# SC_1.net
KiCad netlist of a schematic drawn in EAGLE
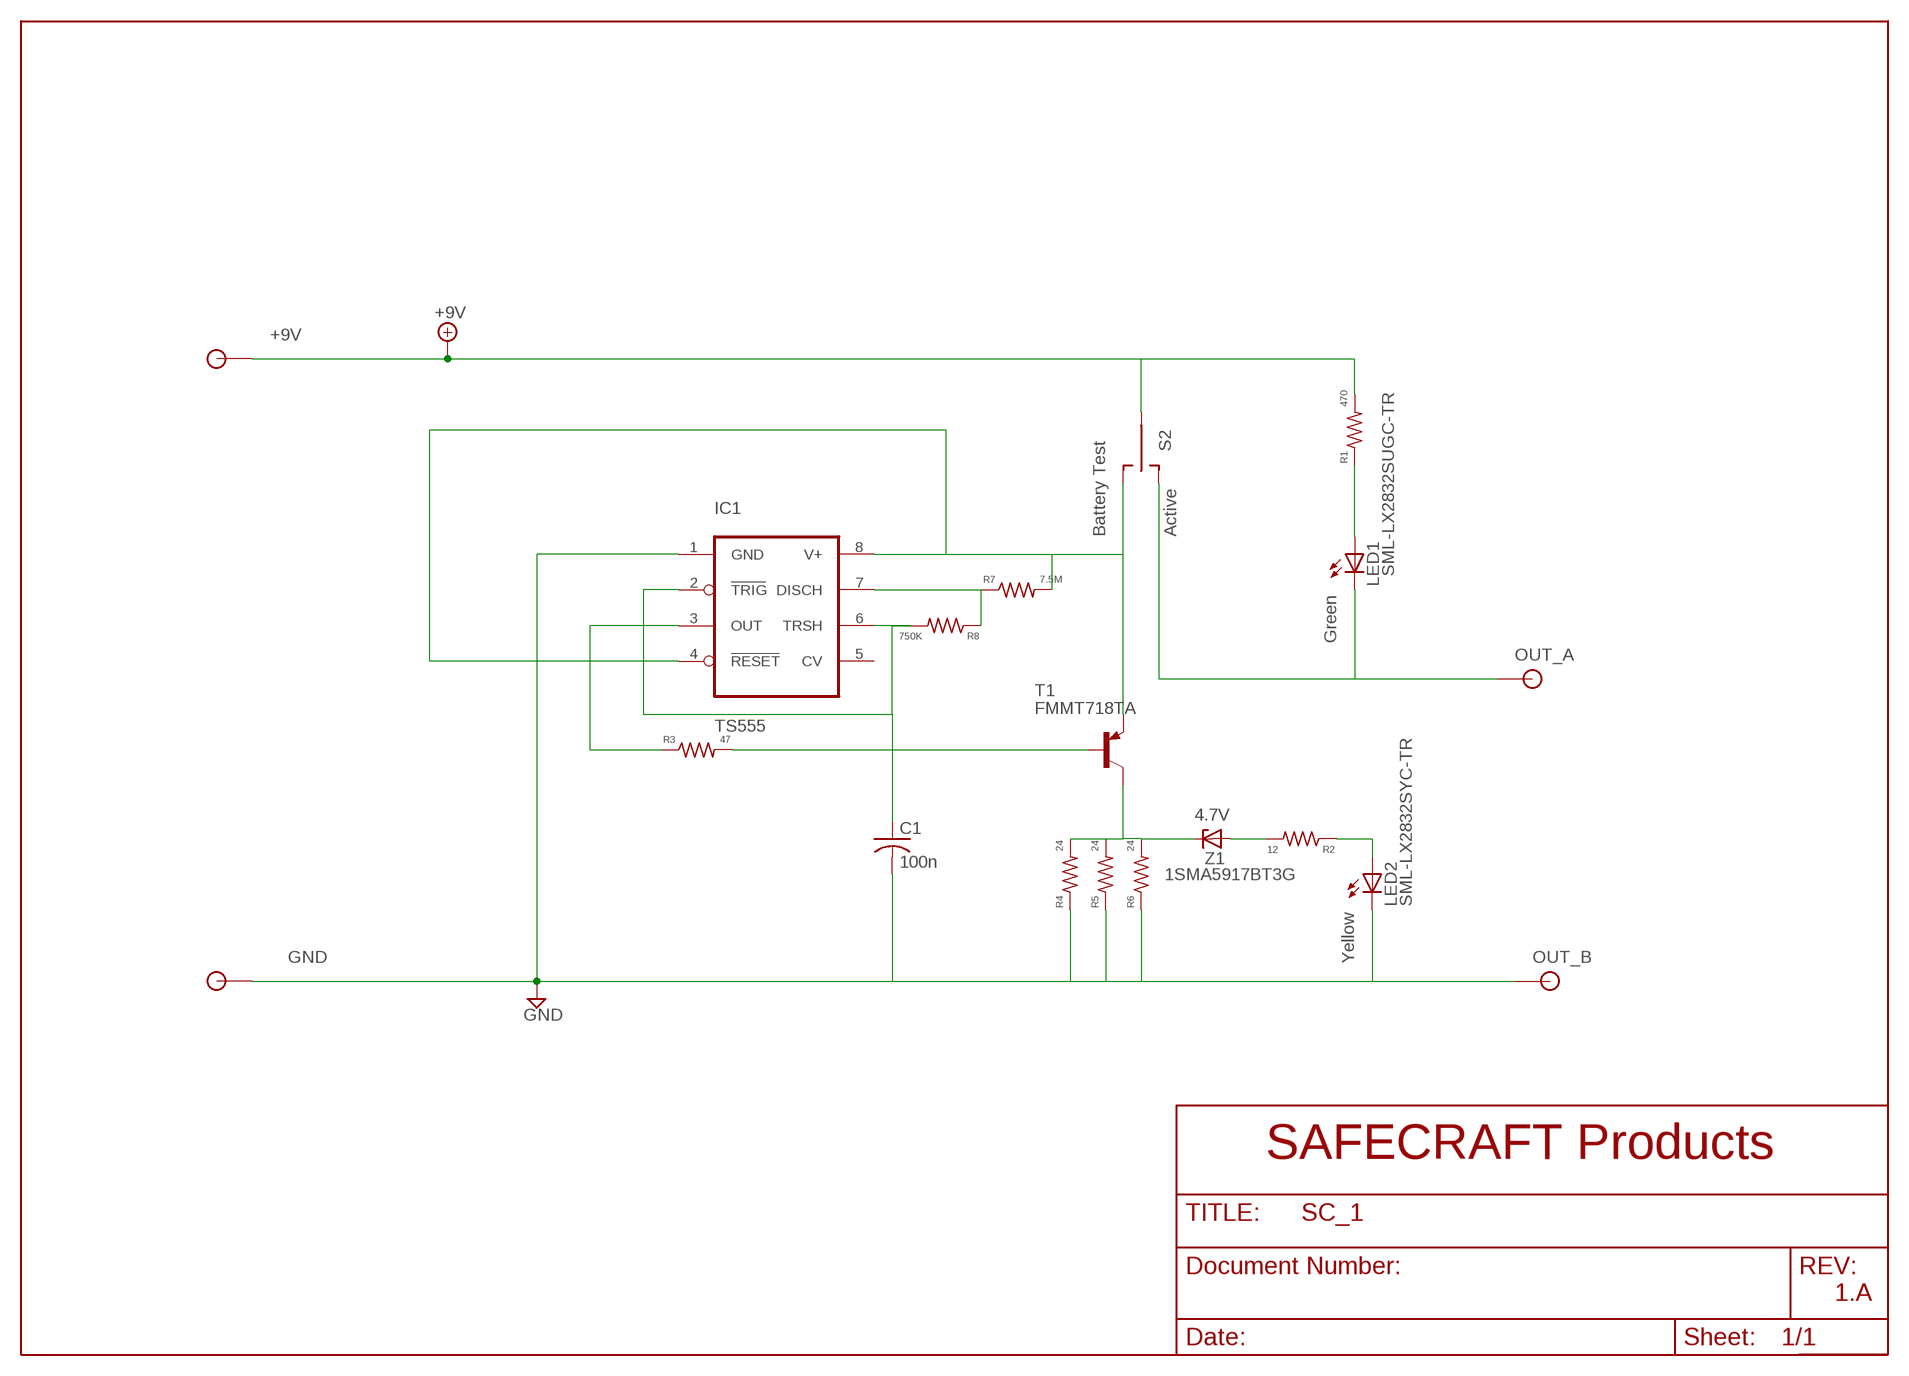
[diagram p0: schematic, sheet 1]

(export (version "E")
  (design (tool "Eeschema 10.0.6"))
  (components
    (comp (ref "C1")
      (value "100n")
      (footprint "eagle-import:C0805")
      (libsource (lib "eagle-import") (part "C-USC0805"))
    )
    (comp (ref "IC1")
      (value "TS555")
      (footprint "eagle-import:SO08")
      (libsource (lib "eagle-import") (part "ICM7555SO08"))
    )
    (comp (ref "LED1")
      (value "SML-LX2832SUGC-TR")
      (footprint "eagle-import:P-LCC-2")
      (libsource (lib "eagle-import") (part "LEDP-LCC-2"))
    )
    (comp (ref "LED2")
      (value "SML-LX2832SYC-TR")
      (footprint "eagle-import:P-LCC-2")
      (libsource (lib "eagle-import") (part "LEDP-LCC-2"))
    )
    (comp (ref "R1")
      (value "470")
      (footprint "eagle-import:R0805")
      (libsource (lib "eagle-import") (part "R-US_R0805"))
    )
    (comp (ref "R2")
      (value "12")
      (footprint "eagle-import:R0805")
      (libsource (lib "eagle-import") (part "R-US_R0805"))
    )
    (comp (ref "R3")
      (value "47")
      (footprint "eagle-import:R0805")
      (libsource (lib "eagle-import") (part "R-US_R0805"))
    )
    (comp (ref "R4")
      (value "24")
      (footprint "eagle-import:R1206")
      (libsource (lib "eagle-import") (part "R-US_R1206"))
    )
    (comp (ref "R5")
      (value "24")
      (footprint "eagle-import:R1206")
      (libsource (lib "eagle-import") (part "R-US_R1206"))
    )
    (comp (ref "R6")
      (value "24")
      (footprint "eagle-import:R1206")
      (libsource (lib "eagle-import") (part "R-US_R1206"))
    )
    (comp (ref "R7")
      (value "7.5M")
      (footprint "eagle-import:R0805")
      (libsource (lib "eagle-import") (part "R-US_R0805"))
    )
    (comp (ref "R8")
      (value "750K")
      (footprint "eagle-import:R0805")
      (libsource (lib "eagle-import") (part "R-US_R0805"))
    )
    (comp (ref "S2")
      (value "TL39POB")
      (footprint "eagle-import:TL3XPO_NOHOLES")
      (libsource (lib "eagle-import") (part "TL39POB"))
    )
    (comp (ref "T1")
      (value "FMMT718TA")
      (footprint "eagle-import:SOT23-BEC")
      (libsource (lib "eagle-import") (part "-PNP-SOT23-BECBC807-16"))
    )
    (comp (ref "U$1")
      (value "SOLDERPAD_NOHOLE")
      (footprint "eagle-import:SOLDERPAD_NOHOLES")
      (libsource (lib "eagle-import") (part "SOLDERPAD_NOHOLE"))
    )
    (comp (ref "U$2")
      (value "SOLDERPAD_NOHOLE")
      (footprint "eagle-import:SOLDERPAD_NOHOLES")
      (libsource (lib "eagle-import") (part "SOLDERPAD_NOHOLE"))
    )
    (comp (ref "U$3")
      (value "SOLDERPAD_NOHOLE")
      (footprint "eagle-import:SOLDERPAD_NOHOLES")
      (libsource (lib "eagle-import") (part "SOLDERPAD_NOHOLE"))
    )
    (comp (ref "U$4")
      (value "SOLDERPAD_NOHOLE")
      (footprint "eagle-import:SOLDERPAD_NOHOLES")
      (libsource (lib "eagle-import") (part "SOLDERPAD_NOHOLE"))
    )
    (comp (ref "Z1")
      (value "1SMA5917BT3G")
      (footprint "eagle-import:SMB")
      (libsource (lib "eagle-import") (part "ZENER-DIODESMB"))
    )
  )
  (nets
    (net (code "1") (name "+9V") (class "Default")
      (node (ref "R1") (pin "2") (pinfunction "2_2") (pintype "passive"))
      (node (ref "S2") (pin "P$2") (pinfunction "P_P$2") (pintype "passive"))
      (node (ref "U$3") (pin "P$1") (pinfunction "P$1_P$1") (pintype "bidirectional"))
    )
    (net (code "2") (name "/OUT_A") (class "Default")
      (node (ref "LED1") (pin "C") (pinfunction "C_C") (pintype "passive"))
      (node (ref "S2") (pin "P$1") (pinfunction "O_P$1") (pintype "passive"))
      (node (ref "U$1") (pin "P$1") (pinfunction "P$1_P$1") (pintype "bidirectional"))
    )
    (net (code "3") (name "GND") (class "Default")
      (node (ref "C1") (pin "2") (pinfunction "2_2") (pintype "passive"))
      (node (ref "IC1") (pin "1") (pinfunction "GND_1") (pintype "power_in"))
      (node (ref "LED2") (pin "C") (pinfunction "C_C") (pintype "passive"))
      (node (ref "R4") (pin "1") (pinfunction "1_1") (pintype "passive"))
      (node (ref "R5") (pin "1") (pinfunction "1_1") (pintype "passive"))
      (node (ref "R6") (pin "1") (pinfunction "1_1") (pintype "passive"))
      (node (ref "U$2") (pin "P$1") (pinfunction "P$1_P$1") (pintype "bidirectional"))
      (node (ref "U$4") (pin "P$1") (pinfunction "P$1_P$1") (pintype "bidirectional"))
    )
    (net (code "4") (name "Net-(IC1-DISCH)") (class "Default")
      (node (ref "IC1") (pin "7") (pinfunction "DISCH_7") (pintype "input"))
      (node (ref "R7") (pin "1") (pinfunction "1_1") (pintype "passive"))
      (node (ref "R8") (pin "1") (pinfunction "1_1") (pintype "passive"))
    )
    (net (code "5") (name "Net-(IC1-OUT)") (class "Default")
      (node (ref "IC1") (pin "3") (pinfunction "OUT_3") (pintype "output"))
      (node (ref "R3") (pin "1") (pinfunction "1_1") (pintype "passive"))
    )
    (net (code "6") (name "Net-(IC1-RESET)") (class "Default")
      (node (ref "IC1") (pin "4") (pinfunction "RESET_4") (pintype "input"))
      (node (ref "IC1") (pin "8") (pinfunction "V+_8") (pintype "power_in"))
      (node (ref "R7") (pin "2") (pinfunction "2_2") (pintype "passive"))
      (node (ref "S2") (pin "P$3") (pinfunction "S_P$3") (pintype "passive"))
      (node (ref "T1") (pin "E") (pinfunction "E_E") (pintype "passive"))
    )
    (net (code "7") (name "Net-(IC1-TRIG)") (class "Default")
      (node (ref "C1") (pin "1") (pinfunction "1_1") (pintype "passive"))
      (node (ref "IC1") (pin "2") (pinfunction "TRIG_2") (pintype "bidirectional"))
      (node (ref "IC1") (pin "6") (pinfunction "TRSH_6") (pintype "input"))
      (node (ref "R8") (pin "2") (pinfunction "2_2") (pintype "passive"))
    )
    (net (code "8") (name "Net-(LED1-PadA)") (class "Default")
      (node (ref "LED1") (pin "A") (pinfunction "A_A") (pintype "passive"))
      (node (ref "R1") (pin "1") (pinfunction "1_1") (pintype "passive"))
    )
    (net (code "9") (name "Net-(LED2-PadA)") (class "Default")
      (node (ref "LED2") (pin "A") (pinfunction "A_A") (pintype "passive"))
      (node (ref "R2") (pin "1") (pinfunction "1_1") (pintype "passive"))
    )
    (net (code "10") (name "Net-(R2-Pad2)") (class "Default")
      (node (ref "R2") (pin "2") (pinfunction "2_2") (pintype "passive"))
      (node (ref "Z1") (pin "A") (pinfunction "A_A") (pintype "passive"))
    )
    (net (code "11") (name "Net-(R3-Pad2)") (class "Default")
      (node (ref "R3") (pin "2") (pinfunction "2_2") (pintype "passive"))
      (node (ref "T1") (pin "B") (pinfunction "B_B") (pintype "passive"))
    )
    (net (code "12") (name "Net-(R4-Pad2)") (class "Default")
      (node (ref "R4") (pin "2") (pinfunction "2_2") (pintype "passive"))
      (node (ref "R5") (pin "2") (pinfunction "2_2") (pintype "passive"))
      (node (ref "R6") (pin "2") (pinfunction "2_2") (pintype "passive"))
      (node (ref "T1") (pin "C") (pinfunction "C_C") (pintype "passive"))
      (node (ref "Z1") (pin "C") (pinfunction "C_C") (pintype "passive"))
    )
    (net (code "13") (name "unconnected-(IC1-CV-Pad5)") (class "Default")
      (node (ref "IC1") (pin "5") (pinfunction "CV_5") (pintype "passive"))
    )
  )
)
